# 2_-Connector_Page.net
KiCad netlist of a schematic drawn in Altium Designer
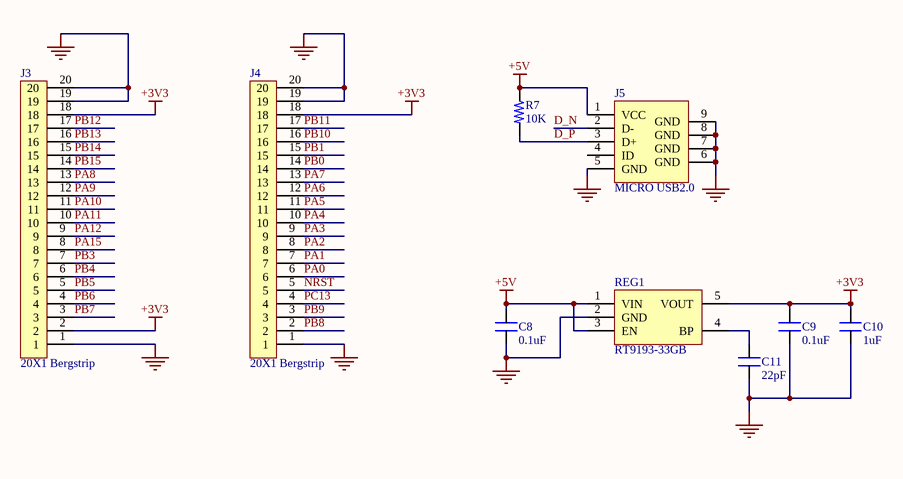
[diagram p0: [2]-Connector_Page.SchDoc]

(export (version "E")
  (design (tool "Eeschema 10.0.6"))
  (components
    (comp (ref "C8")
      (value "0.1uF")
      (footprint "CAP_0805")
      (description "0.1µF ±5% 50V Ceramic Capacitor X7R 0805 (2012 Metric)")
      (fields
        (field (name "MANUFACTURER") "KEMET")
        (field (name "MANUFACTURING PART NUMBER") "C0805C104J5RACTU")
      )
      (libsource (lib "STM_INT_LIB") (part "CAP_0.1uF-50V-5%-0805"))
    )
    (comp (ref "C9")
      (value "0.1uF")
      (footprint "CAP_0805")
      (description "0.1µF ±5% 50V Ceramic Capacitor X7R 0805 (2012 Metric)")
      (fields
        (field (name "MANUFACTURER") "KEMET")
        (field (name "MANUFACTURING PART NUMBER") "C0805C104J5RACTU")
      )
      (libsource (lib "STM_INT_LIB") (part "CAP_0.1uF-50V-5%-0805"))
    )
    (comp (ref "C10")
      (value "1uF")
      (footprint "CAP_0805")
      (description "1µF ±5% 50V Ceramic Capacitor X7R 0805 (2012 Metric)")
      (fields
        (field (name "MANUFACTURER") "Yageo")
        (field (name "MANUFACTURING PART NUMBER") "CC0805JKX7R9BB105")
      )
      (libsource (lib "STM_INT_LIB") (part "CAP_1uF-50V-5%-0805"))
    )
    (comp (ref "C11")
      (value "22pF")
      (footprint "CAP_0805")
      (description "22pF ±5% 50V Ceramic Capacitor C0G, NP0 0805 (2012 Metric)")
      (fields
        (field (name "MANUFACTURER") "KEMET")
        (field (name "MANUFACTURER PART NUMBER") "C0805C220J5GACTU")
      )
      (libsource (lib "STM_INT_LIB") (part "CAP_22pF-50V-5%-0805"))
    )
    (comp (ref "J3")
      (value "20X1 Bergstrip")
      (footprint "CON20_100_40D72_TH_ST")
      (description "20 pin, 1 row, 2.54mm pitch bergstrip")
      (fields (field (name "MANUFACTURER") "NA"))
      (libsource (lib "STM_INT_LIB") (part "CON-BS-PLG_20X1-100-TH-ST"))
    )
    (comp (ref "J4")
      (value "20X1 Bergstrip")
      (footprint "CON20_100_40D72_TH_ST")
      (description "20 pin, 1 row, 2.54mm pitch bergstrip")
      (fields (field (name "MANUFACTURER") "NA"))
      (libsource (lib "STM_INT_LIB") (part "CON-BS-PLG_20X1-100-TH-ST"))
    )
    (comp (ref "J5")
      (value "MICRO USB2.0")
      (footprint "CON_10118192-0001LF_SMD")
      (description "USB - micro B USB 2.0 Receptacle Connector 5 Position Surface Mount, Right Angle")
      (fields
        (field (name "MANUFACTURER") "Amphenol ICC (FCI)")
        (field (name "MANUFACTURING PART NUMBER") "10118192-0002LF")
      )
      (libsource (lib "STM_INT_LIB") (part "CON-USB_10118192-0002LF-SMD"))
    )
    (comp (ref "R7")
      (value "10K")
      (footprint "RES_0805")
      (description "10 kOhms ±1% 0.125W, 1/8W Chip Resistor 0805 (2012 Metric) Moisture Resistant Thick Film")
      (fields
        (field (name "MANUFACTURER") "Yageo")
        (field (name "MANUFACTURING PART NUMBER") "RC0805FR-0710KL")
      )
      (libsource (lib "STM_INT_LIB") (part "RES_10K-0.125W-1%-0805"))
    )
    (comp (ref "REG1")
      (value "RT9193-33GB")
      (footprint "SOT23-5")
      (description "Linear Voltage Regulator IC 1 Output 300mA SOT-23-5")
      (fields (field (name "MANUFACTURER") "Richtek USA Inc."))
      (libsource (lib "STM_INT_LIB") (part "REG_3.3V-5.5V-0.3A-SOT-23-5"))
    )
  )
  (nets
    (net (code "1") (name "+3V3") (class "Default")
      (node (ref "C10") (pin "2") (pinfunction "2_2") (pintype "passive"))
      (node (ref "C9") (pin "2") (pinfunction "2_2") (pintype "passive"))
      (node (ref "J3") (pin "18") (pinfunction "18_18") (pintype "passive"))
      (node (ref "J3") (pin "2") (pinfunction "2_2") (pintype "passive"))
      (node (ref "J4") (pin "18") (pinfunction "18_18") (pintype "passive"))
      (node (ref "REG1") (pin "5") (pinfunction "VOUT_5") (pintype "passive"))
    )
    (net (code "2") (name "+5V") (class "Default")
      (node (ref "C8") (pin "2") (pinfunction "2_2") (pintype "passive"))
      (node (ref "J5") (pin "1") (pinfunction "VCC_1") (pintype "passive"))
      (node (ref "R7") (pin "2") (pinfunction "2_2") (pintype "passive"))
      (node (ref "REG1") (pin "1") (pinfunction "VIN_1") (pintype "passive"))
      (node (ref "REG1") (pin "3") (pinfunction "EN_3") (pintype "passive"))
    )
    (net (code "3") (name "/D_N") (class "Default")
      (node (ref "J5") (pin "2") (pinfunction "D-_2") (pintype "passive"))
    )
    (net (code "4") (name "/D_P") (class "Default")
      (node (ref "J5") (pin "3") (pinfunction "D+_3") (pintype "passive"))
      (node (ref "R7") (pin "1") (pinfunction "1_1") (pintype "passive"))
    )
    (net (code "5") (name "/NRST") (class "Default")
      (node (ref "J4") (pin "5") (pinfunction "5_5") (pintype "passive"))
    )
    (net (code "6") (name "/PA0") (class "Default")
      (node (ref "J4") (pin "6") (pinfunction "6_6") (pintype "passive"))
    )
    (net (code "7") (name "/PA1") (class "Default")
      (node (ref "J4") (pin "7") (pinfunction "7_7") (pintype "passive"))
    )
    (net (code "8") (name "/PA2") (class "Default")
      (node (ref "J4") (pin "8") (pinfunction "8_8") (pintype "passive"))
    )
    (net (code "9") (name "/PA3") (class "Default")
      (node (ref "J4") (pin "9") (pinfunction "9_9") (pintype "passive"))
    )
    (net (code "10") (name "/PA4") (class "Default")
      (node (ref "J4") (pin "10") (pinfunction "10_10") (pintype "passive"))
    )
    (net (code "11") (name "/PA5") (class "Default")
      (node (ref "J4") (pin "11") (pinfunction "11_11") (pintype "passive"))
    )
    (net (code "12") (name "/PA6") (class "Default")
      (node (ref "J4") (pin "12") (pinfunction "12_12") (pintype "passive"))
    )
    (net (code "13") (name "/PA7") (class "Default")
      (node (ref "J4") (pin "13") (pinfunction "13_13") (pintype "passive"))
    )
    (net (code "14") (name "/PA8") (class "Default")
      (node (ref "J3") (pin "13") (pinfunction "13_13") (pintype "passive"))
    )
    (net (code "15") (name "/PA9") (class "Default")
      (node (ref "J3") (pin "12") (pinfunction "12_12") (pintype "passive"))
    )
    (net (code "16") (name "/PA10") (class "Default")
      (node (ref "J3") (pin "11") (pinfunction "11_11") (pintype "passive"))
    )
    (net (code "17") (name "/PA11") (class "Default")
      (node (ref "J3") (pin "10") (pinfunction "10_10") (pintype "passive"))
    )
    (net (code "18") (name "/PA12") (class "Default")
      (node (ref "J3") (pin "9") (pinfunction "9_9") (pintype "passive"))
    )
    (net (code "19") (name "/PA15") (class "Default")
      (node (ref "J3") (pin "8") (pinfunction "8_8") (pintype "passive"))
    )
    (net (code "20") (name "/PB0") (class "Default")
      (node (ref "J4") (pin "14") (pinfunction "14_14") (pintype "passive"))
    )
    (net (code "21") (name "/PB1") (class "Default")
      (node (ref "J4") (pin "15") (pinfunction "15_15") (pintype "passive"))
    )
    (net (code "22") (name "/PB3") (class "Default")
      (node (ref "J3") (pin "7") (pinfunction "7_7") (pintype "passive"))
    )
    (net (code "23") (name "/PB4") (class "Default")
      (node (ref "J3") (pin "6") (pinfunction "6_6") (pintype "passive"))
    )
    (net (code "24") (name "/PB5") (class "Default")
      (node (ref "J3") (pin "5") (pinfunction "5_5") (pintype "passive"))
    )
    (net (code "25") (name "/PB6") (class "Default")
      (node (ref "J3") (pin "4") (pinfunction "4_4") (pintype "passive"))
    )
    (net (code "26") (name "/PB7") (class "Default")
      (node (ref "J3") (pin "3") (pinfunction "3_3") (pintype "passive"))
    )
    (net (code "27") (name "/PB8") (class "Default")
      (node (ref "J4") (pin "2") (pinfunction "2_2") (pintype "passive"))
    )
    (net (code "28") (name "/PB9") (class "Default")
      (node (ref "J4") (pin "3") (pinfunction "3_3") (pintype "passive"))
    )
    (net (code "29") (name "/PB10") (class "Default")
      (node (ref "J4") (pin "16") (pinfunction "16_16") (pintype "passive"))
    )
    (net (code "30") (name "/PB11") (class "Default")
      (node (ref "J4") (pin "17") (pinfunction "17_17") (pintype "passive"))
    )
    (net (code "31") (name "/PB12") (class "Default")
      (node (ref "J3") (pin "17") (pinfunction "17_17") (pintype "passive"))
    )
    (net (code "32") (name "/PB13") (class "Default")
      (node (ref "J3") (pin "16") (pinfunction "16_16") (pintype "passive"))
    )
    (net (code "33") (name "/PB14") (class "Default")
      (node (ref "J3") (pin "15") (pinfunction "15_15") (pintype "passive"))
    )
    (net (code "34") (name "/PB15") (class "Default")
      (node (ref "J3") (pin "14") (pinfunction "14_14") (pintype "passive"))
    )
    (net (code "35") (name "/PC13") (class "Default")
      (node (ref "J4") (pin "4") (pinfunction "4_4") (pintype "passive"))
    )
    (net (code "36") (name "GND") (class "Default")
      (node (ref "C10") (pin "1") (pinfunction "1_1") (pintype "passive"))
      (node (ref "C11") (pin "1") (pinfunction "1_1") (pintype "passive"))
      (node (ref "C8") (pin "1") (pinfunction "1_1") (pintype "passive"))
      (node (ref "C9") (pin "1") (pinfunction "1_1") (pintype "passive"))
      (node (ref "J3") (pin "1") (pinfunction "1_1") (pintype "passive"))
      (node (ref "J3") (pin "19") (pinfunction "19_19") (pintype "passive"))
      (node (ref "J3") (pin "20") (pinfunction "20_20") (pintype "passive"))
      (node (ref "J4") (pin "1") (pinfunction "1_1") (pintype "passive"))
      (node (ref "J4") (pin "19") (pinfunction "19_19") (pintype "passive"))
      (node (ref "J4") (pin "20") (pinfunction "20_20") (pintype "passive"))
      (node (ref "J5") (pin "5") (pinfunction "GND_5") (pintype "passive"))
      (node (ref "J5") (pin "6") (pinfunction "GND_6") (pintype "passive"))
      (node (ref "J5") (pin "7") (pinfunction "GND_7") (pintype "passive"))
      (node (ref "J5") (pin "8") (pinfunction "GND_8") (pintype "passive"))
      (node (ref "J5") (pin "9") (pinfunction "GND_9") (pintype "passive"))
      (node (ref "REG1") (pin "2") (pinfunction "GND_2") (pintype "passive"))
    )
    (net (code "37") (name "Net-(REG1-BP)") (class "Default")
      (node (ref "C11") (pin "2") (pinfunction "2_2") (pintype "passive"))
      (node (ref "REG1") (pin "4") (pinfunction "BP_4") (pintype "passive"))
    )
    (net (code "38") (name "unconnected-(J5-ID-Pad4)") (class "Default")
      (node (ref "J5") (pin "4") (pinfunction "ID_4") (pintype "passive"))
    )
  )
)
